# SpiCurrent-wimpy.net
KiCad netlist of a schematic drawn in EAGLE
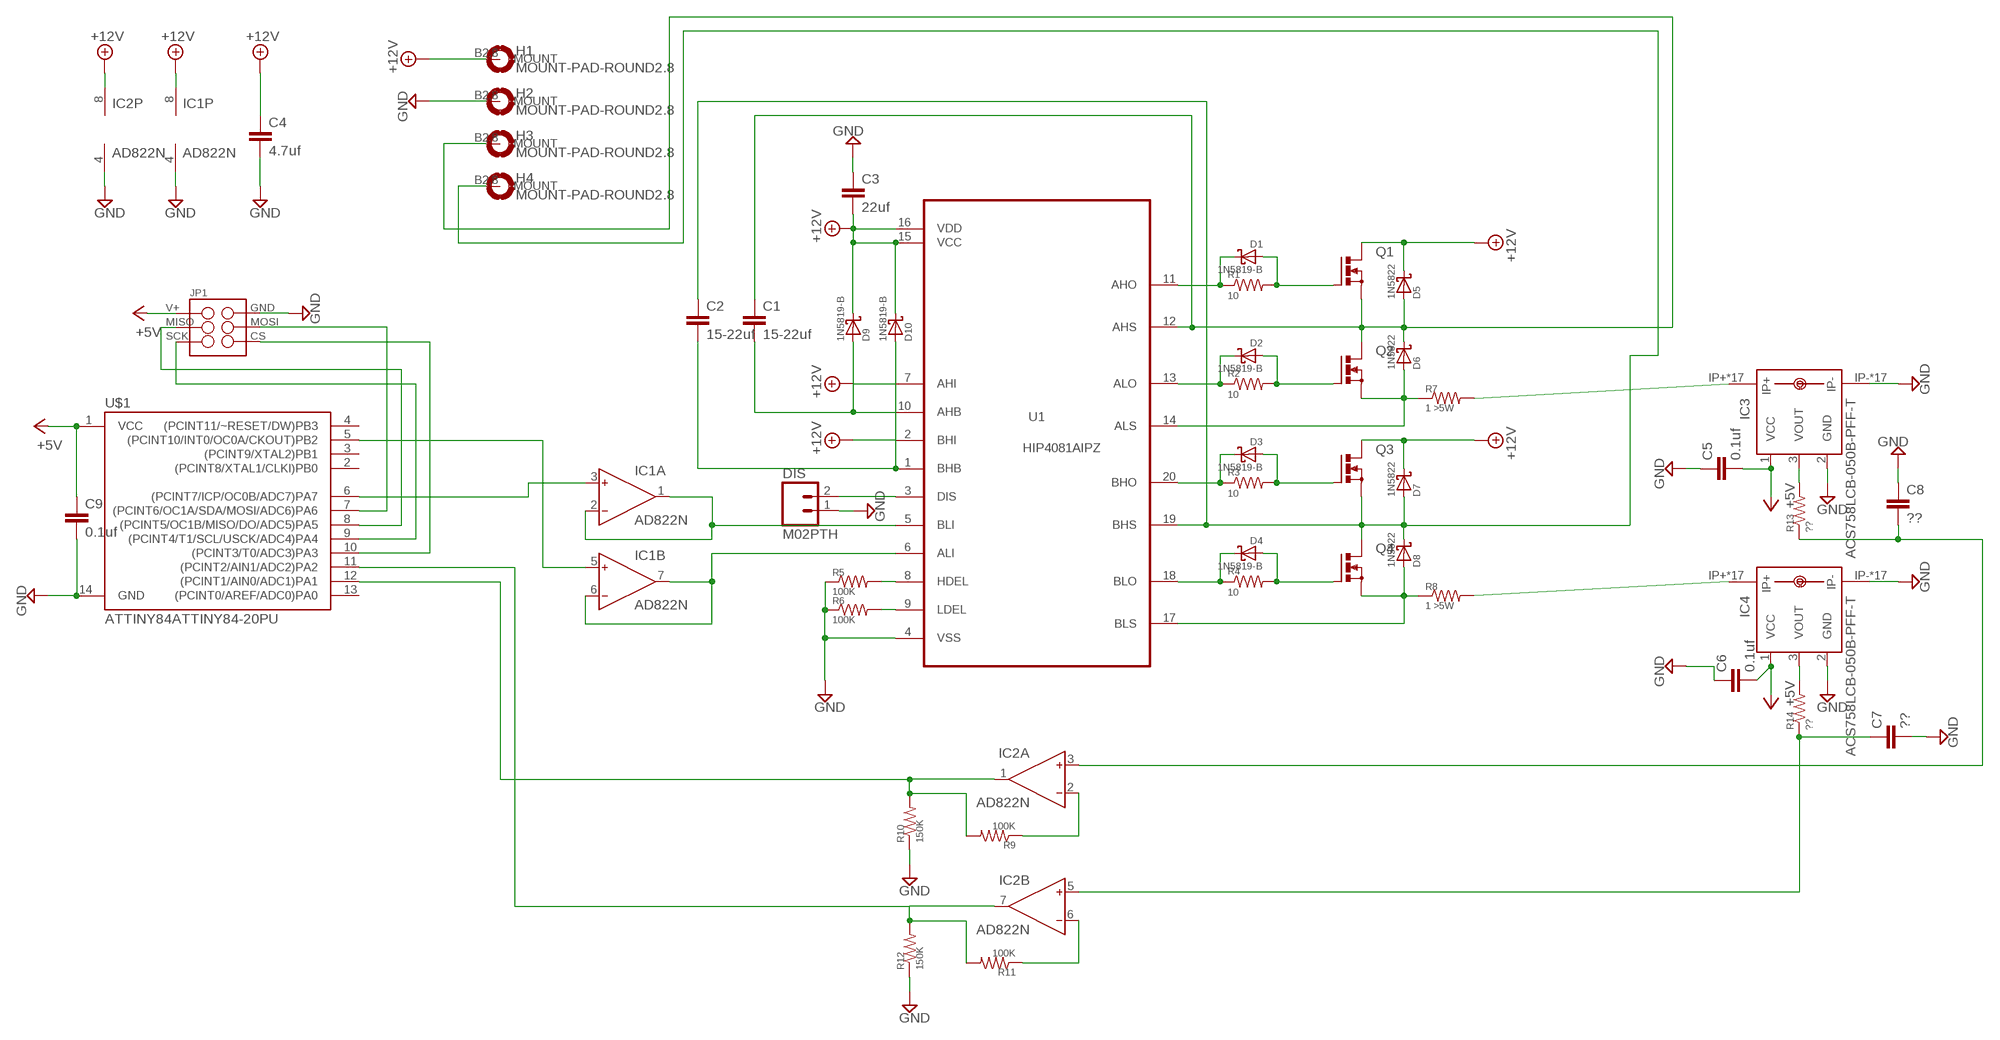
[diagram p0: schematic, sheet 1]

(export (version "E")
  (design (tool "Eeschema 10.0.6"))
  (components
    (comp (ref "C1")
      (value "15-22uf")
      (footprint "eagle-import:C050-055X075")
      (libsource (lib "eagle-import") (part "C-EU050-055X075"))
    )
    (comp (ref "C2")
      (value "15-22uf")
      (footprint "eagle-import:C050-055X075")
      (libsource (lib "eagle-import") (part "C-EU050-055X075"))
    )
    (comp (ref "C3")
      (value "22uf")
      (footprint "eagle-import:C050-055X075")
      (libsource (lib "eagle-import") (part "C-EU050-055X075"))
    )
    (comp (ref "C4")
      (value "4.7uf")
      (footprint "eagle-import:C050-055X075")
      (libsource (lib "eagle-import") (part "C-EU050-055X075"))
    )
    (comp (ref "C5")
      (value "0.1uf")
      (footprint "eagle-import:C050-055X075")
      (libsource (lib "eagle-import") (part "C-EU050-055X075"))
    )
    (comp (ref "C6")
      (value "0.1uf")
      (footprint "eagle-import:C050-055X075")
      (libsource (lib "eagle-import") (part "C-EU050-055X075"))
    )
    (comp (ref "C7")
      (value "??")
      (footprint "eagle-import:C050-055X075")
      (libsource (lib "eagle-import") (part "C-EU050-055X075"))
    )
    (comp (ref "C8")
      (value "??")
      (footprint "eagle-import:C050-055X075")
      (libsource (lib "eagle-import") (part "C-EU050-055X075"))
    )
    (comp (ref "C9")
      (value "0.1uf")
      (footprint "eagle-import:C050-055X075")
      (libsource (lib "eagle-import") (part "C-EU050-055X075"))
    )
    (comp (ref "D1")
      (value "1N5819-B")
      (footprint "eagle-import:DO41-7.6")
      (libsource (lib "eagle-import") (part "1N5819-B"))
    )
    (comp (ref "D2")
      (value "1N5819-B")
      (footprint "eagle-import:DO41-7.6")
      (libsource (lib "eagle-import") (part "1N5819-B"))
    )
    (comp (ref "D3")
      (value "1N5819-B")
      (footprint "eagle-import:DO41-7.6")
      (libsource (lib "eagle-import") (part "1N5819-B"))
    )
    (comp (ref "D4")
      (value "1N5819-B")
      (footprint "eagle-import:DO41-7.6")
      (libsource (lib "eagle-import") (part "1N5819-B"))
    )
    (comp (ref "D5")
      (value "1N5822")
      (footprint "eagle-import:DO41-7.6")
      (libsource (lib "eagle-import") (part "1N5819-B"))
    )
    (comp (ref "D6")
      (value "1N5822")
      (footprint "eagle-import:DO41-7.6")
      (libsource (lib "eagle-import") (part "1N5819-B"))
    )
    (comp (ref "D7")
      (value "1N5822")
      (footprint "eagle-import:DO41-7.6")
      (libsource (lib "eagle-import") (part "1N5819-B"))
    )
    (comp (ref "D8")
      (value "1N5822")
      (footprint "eagle-import:DO41-7.6")
      (libsource (lib "eagle-import") (part "1N5819-B"))
    )
    (comp (ref "D9")
      (value "1N5819-B")
      (footprint "eagle-import:DO41-7.6")
      (libsource (lib "eagle-import") (part "1N5819-B"))
    )
    (comp (ref "D10")
      (value "1N5819-B")
      (footprint "eagle-import:DO41-7.6")
      (libsource (lib "eagle-import") (part "1N5819-B"))
    )
    (comp (ref "DIS")
      (value "M02PTH")
      (footprint "eagle-import:1X02")
      (libsource (lib "eagle-import") (part "M02PTH"))
    )
    (comp (ref "H1")
      (value "MOUNT-PAD-ROUND2.8")
      (footprint "eagle-import:2,8-PAD")
      (libsource (lib "eagle-import") (part "MOUNT-PAD-ROUND2.8"))
    )
    (comp (ref "H2")
      (value "MOUNT-PAD-ROUND2.8")
      (footprint "eagle-import:2,8-PAD")
      (libsource (lib "eagle-import") (part "MOUNT-PAD-ROUND2.8"))
    )
    (comp (ref "H3")
      (value "MOUNT-PAD-ROUND2.8")
      (footprint "eagle-import:2,8-PAD")
      (libsource (lib "eagle-import") (part "MOUNT-PAD-ROUND2.8"))
    )
    (comp (ref "H4")
      (value "MOUNT-PAD-ROUND2.8")
      (footprint "eagle-import:2,8-PAD")
      (libsource (lib "eagle-import") (part "MOUNT-PAD-ROUND2.8"))
    )
    (comp (ref "IC1")
      (value "AD822N")
      (footprint "eagle-import:DIL08")
      (libsource (lib "eagle-import") (part "AD822N"))
    )
    (comp (ref "IC2")
      (value "AD822N")
      (footprint "eagle-import:DIL08")
      (libsource (lib "eagle-import") (part "AD822N"))
    )
    (comp (ref "IC3")
      (value "ACS758LCB-050B-PFF-T")
      (footprint "eagle-import:CB-PFF")
      (libsource (lib "eagle-import") (part "ACS758LCB-050B-PFF-T"))
    )
    (comp (ref "IC4")
      (value "ACS758LCB-050B-PFF-T")
      (footprint "eagle-import:CB-PFF")
      (libsource (lib "eagle-import") (part "ACS758LCB-050B-PFF-T"))
    )
    (comp (ref "JP1")
      (value "M03X2SHROUD")
      (footprint "eagle-import:2X3-SPI-SHROUDED")
      (libsource (lib "eagle-import") (part "M03X2SHROUD"))
    )
    (comp (ref "Q1")
      (value "PMOSFET_NTO220BV")
      (footprint "eagle-import:TO220BV")
      (libsource (lib "eagle-import") (part "PMOSFET_NTO220BV"))
    )
    (comp (ref "Q2")
      (value "PMOSFET_NTO220BV")
      (footprint "eagle-import:TO220BV")
      (libsource (lib "eagle-import") (part "PMOSFET_NTO220BV"))
    )
    (comp (ref "Q3")
      (value "PMOSFET_NTO220BV")
      (footprint "eagle-import:TO220BV")
      (libsource (lib "eagle-import") (part "PMOSFET_NTO220BV"))
    )
    (comp (ref "Q4")
      (value "PMOSFET_NTO220BV")
      (footprint "eagle-import:TO220BV")
      (libsource (lib "eagle-import") (part "PMOSFET_NTO220BV"))
    )
    (comp (ref "R1")
      (value "10")
      (footprint "eagle-import:0207_10")
      (libsource (lib "eagle-import") (part "R-US_0207/10"))
    )
    (comp (ref "R2")
      (value "10")
      (footprint "eagle-import:0207_10")
      (libsource (lib "eagle-import") (part "R-US_0207/10"))
    )
    (comp (ref "R3")
      (value "10")
      (footprint "eagle-import:0207_10")
      (libsource (lib "eagle-import") (part "R-US_0207/10"))
    )
    (comp (ref "R4")
      (value "10")
      (footprint "eagle-import:0207_10")
      (libsource (lib "eagle-import") (part "R-US_0207/10"))
    )
    (comp (ref "R5")
      (value "100K")
      (footprint "eagle-import:0207_10")
      (libsource (lib "eagle-import") (part "resistor-custom_R-US_0207/10"))
    )
    (comp (ref "R6")
      (value "100K")
      (footprint "eagle-import:0207_10")
      (libsource (lib "eagle-import") (part "resistor-custom_R-US_0207/10"))
    )
    (comp (ref "R7")
      (value "1 >5W")
      (footprint "eagle-import:VTA54")
      (libsource (lib "eagle-import") (part "resistor-custom_R-US_VTA54"))
    )
    (comp (ref "R8")
      (value "1 >5W")
      (footprint "eagle-import:VTA54")
      (libsource (lib "eagle-import") (part "resistor-custom_R-US_VTA54"))
    )
    (comp (ref "R9")
      (value "100K")
      (footprint "eagle-import:0207_10")
      (libsource (lib "eagle-import") (part "resistor-custom_R-US_0207/10"))
    )
    (comp (ref "R10")
      (value "150K")
      (footprint "eagle-import:0207_10")
      (libsource (lib "eagle-import") (part "resistor-custom_R-US_0207/10"))
    )
    (comp (ref "R11")
      (value "100K")
      (footprint "eagle-import:0207_10")
      (libsource (lib "eagle-import") (part "resistor-custom_R-US_0207/10"))
    )
    (comp (ref "R12")
      (value "150K")
      (footprint "eagle-import:0207_10")
      (libsource (lib "eagle-import") (part "resistor-custom_R-US_0207/10"))
    )
    (comp (ref "R13")
      (value "??")
      (footprint "eagle-import:0207_10")
      (libsource (lib "eagle-import") (part "resistor-custom_R-US_0207/10"))
    )
    (comp (ref "R14")
      (value "??")
      (footprint "eagle-import:0207_10")
      (libsource (lib "eagle-import") (part "resistor-custom_R-US_0207/10"))
    )
    (comp (ref "U$1")
      (value "ATTINY84ATTINY84-20PU")
      (footprint "eagle-import:DIL14")
      (libsource (lib "eagle-import") (part "ATTINY84ATTINY84-20PU"))
    )
    (comp (ref "U1")
      (value "HIP4081AIPZ")
      (footprint "eagle-import:DIP254P762X533-20")
      (libsource (lib "eagle-import") (part "HIP4081AIPZ"))
    )
  )
  (nets
    (net (code "1") (name "+5V") (class "Default")
      (node (ref "C5") (pin "2") (pinfunction "2_2") (pintype "passive"))
      (node (ref "C6") (pin "2") (pinfunction "2_2") (pintype "passive"))
      (node (ref "C9") (pin "1") (pinfunction "1_1") (pintype "passive"))
      (node (ref "IC3") (pin "1") (pinfunction "VCC_1") (pintype "power_in"))
      (node (ref "IC4") (pin "1") (pinfunction "VCC_1") (pintype "power_in"))
      (node (ref "JP1") (pin "1") (pinfunction "1_1") (pintype "bidirectional"))
      (node (ref "U$1") (pin "1") (pinfunction "VCC_1") (pintype "bidirectional"))
    )
    (net (code "2") (name "+12V") (class "Default")
      (node (ref "C3") (pin "2") (pinfunction "2_2") (pintype "passive"))
      (node (ref "C4") (pin "1") (pinfunction "1_1") (pintype "passive"))
      (node (ref "D10") (pin "C") (pinfunction "C_C") (pintype "passive"))
      (node (ref "D5") (pin "C") (pinfunction "C_C") (pintype "passive"))
      (node (ref "D7") (pin "C") (pinfunction "C_C") (pintype "passive"))
      (node (ref "D9") (pin "C") (pinfunction "C_C") (pintype "passive"))
      (node (ref "H1") (pin "B2,8") (pinfunction "MOUNT_B2,8") (pintype "passive"))
      (node (ref "IC1") (pin "8") (pinfunction "V+_8") (pintype "power_in"))
      (node (ref "IC2") (pin "8") (pinfunction "V+_8") (pintype "power_in"))
      (node (ref "Q1") (pin "D") (pinfunction "D_D") (pintype "passive"))
      (node (ref "Q3") (pin "D") (pinfunction "D_D") (pintype "passive"))
      (node (ref "U1") (pin "15") (pinfunction "VCC_15") (pintype "power_in"))
      (node (ref "U1") (pin "16") (pinfunction "VDD_16") (pintype "power_in"))
      (node (ref "U1") (pin "2") (pinfunction "BHI_2") (pintype "input"))
      (node (ref "U1") (pin "7") (pinfunction "AHI_7") (pintype "input"))
    )
    (net (code "3") (name "GND") (class "Default")
      (node (ref "C3") (pin "1") (pinfunction "1_1") (pintype "passive"))
      (node (ref "C4") (pin "2") (pinfunction "2_2") (pintype "passive"))
      (node (ref "C5") (pin "1") (pinfunction "1_1") (pintype "passive"))
      (node (ref "C6") (pin "1") (pinfunction "1_1") (pintype "passive"))
      (node (ref "C7") (pin "2") (pinfunction "2_2") (pintype "passive"))
      (node (ref "C8") (pin "1") (pinfunction "1_1") (pintype "passive"))
      (node (ref "C9") (pin "2") (pinfunction "2_2") (pintype "passive"))
      (node (ref "DIS") (pin "1") (pinfunction "1_1") (pintype "passive"))
      (node (ref "H2") (pin "B2,8") (pinfunction "MOUNT_B2,8") (pintype "passive"))
      (node (ref "IC1") (pin "4") (pinfunction "V-_4") (pintype "power_in"))
      (node (ref "IC2") (pin "4") (pinfunction "V-_4") (pintype "power_in"))
      (node (ref "IC3") (pin "2") (pinfunction "GND_2") (pintype "power_in"))
      (node (ref "IC3") (pin "IP-") (pinfunction "IP-_IP-") (pintype "passive"))
      (node (ref "IC3") (pin "IP-@10") (pinfunction "IP-_IP-@10") (pintype "passive"))
      (node (ref "IC3") (pin "IP-@11") (pinfunction "IP-_IP-@11") (pintype "passive"))
      (node (ref "IC3") (pin "IP-@12") (pinfunction "IP-_IP-@12") (pintype "passive"))
      (node (ref "IC3") (pin "IP-@13") (pinfunction "IP-_IP-@13") (pintype "passive"))
      (node (ref "IC3") (pin "IP-@14") (pinfunction "IP-_IP-@14") (pintype "passive"))
      (node (ref "IC3") (pin "IP-@15") (pinfunction "IP-_IP-@15") (pintype "passive"))
      (node (ref "IC3") (pin "IP-@16") (pinfunction "IP-_IP-@16") (pintype "passive"))
      (node (ref "IC3") (pin "IP-@17") (pinfunction "IP-_IP-@17") (pintype "passive"))
      (node (ref "IC3") (pin "IP-@2") (pinfunction "IP-_IP-@2") (pintype "passive"))
      (node (ref "IC3") (pin "IP-@3") (pinfunction "IP-_IP-@3") (pintype "passive"))
      (node (ref "IC3") (pin "IP-@4") (pinfunction "IP-_IP-@4") (pintype "passive"))
      (node (ref "IC3") (pin "IP-@5") (pinfunction "IP-_IP-@5") (pintype "passive"))
      (node (ref "IC3") (pin "IP-@6") (pinfunction "IP-_IP-@6") (pintype "passive"))
      (node (ref "IC3") (pin "IP-@7") (pinfunction "IP-_IP-@7") (pintype "passive"))
      (node (ref "IC3") (pin "IP-@8") (pinfunction "IP-_IP-@8") (pintype "passive"))
      (node (ref "IC3") (pin "IP-@9") (pinfunction "IP-_IP-@9") (pintype "passive"))
      (node (ref "IC4") (pin "2") (pinfunction "GND_2") (pintype "power_in"))
      (node (ref "IC4") (pin "IP-") (pinfunction "IP-_IP-") (pintype "passive"))
      (node (ref "IC4") (pin "IP-@10") (pinfunction "IP-_IP-@10") (pintype "passive"))
      (node (ref "IC4") (pin "IP-@11") (pinfunction "IP-_IP-@11") (pintype "passive"))
      (node (ref "IC4") (pin "IP-@12") (pinfunction "IP-_IP-@12") (pintype "passive"))
      (node (ref "IC4") (pin "IP-@13") (pinfunction "IP-_IP-@13") (pintype "passive"))
      (node (ref "IC4") (pin "IP-@14") (pinfunction "IP-_IP-@14") (pintype "passive"))
      (node (ref "IC4") (pin "IP-@15") (pinfunction "IP-_IP-@15") (pintype "passive"))
      (node (ref "IC4") (pin "IP-@16") (pinfunction "IP-_IP-@16") (pintype "passive"))
      (node (ref "IC4") (pin "IP-@17") (pinfunction "IP-_IP-@17") (pintype "passive"))
      (node (ref "IC4") (pin "IP-@2") (pinfunction "IP-_IP-@2") (pintype "passive"))
      (node (ref "IC4") (pin "IP-@3") (pinfunction "IP-_IP-@3") (pintype "passive"))
      (node (ref "IC4") (pin "IP-@4") (pinfunction "IP-_IP-@4") (pintype "passive"))
      (node (ref "IC4") (pin "IP-@5") (pinfunction "IP-_IP-@5") (pintype "passive"))
      (node (ref "IC4") (pin "IP-@6") (pinfunction "IP-_IP-@6") (pintype "passive"))
      (node (ref "IC4") (pin "IP-@7") (pinfunction "IP-_IP-@7") (pintype "passive"))
      (node (ref "IC4") (pin "IP-@8") (pinfunction "IP-_IP-@8") (pintype "passive"))
      (node (ref "IC4") (pin "IP-@9") (pinfunction "IP-_IP-@9") (pintype "passive"))
      (node (ref "JP1") (pin "2") (pinfunction "2_2") (pintype "bidirectional"))
      (node (ref "R10") (pin "1") (pinfunction "1_1") (pintype "passive"))
      (node (ref "R12") (pin "1") (pinfunction "1_1") (pintype "passive"))
      (node (ref "R5") (pin "1") (pinfunction "1_1") (pintype "passive"))
      (node (ref "R6") (pin "1") (pinfunction "1_1") (pintype "passive"))
      (node (ref "U$1") (pin "14") (pinfunction "GND_14") (pintype "bidirectional"))
      (node (ref "U1") (pin "4") (pinfunction "VSS_4") (pintype "power_in"))
    )
    (net (code "4") (name "Net-(D1-PadA)") (class "Default")
      (node (ref "D1") (pin "A") (pinfunction "A_A") (pintype "passive"))
      (node (ref "Q1") (pin "G") (pinfunction "G_G") (pintype "passive"))
      (node (ref "R1") (pin "2") (pinfunction "2_2") (pintype "passive"))
    )
    (net (code "5") (name "Net-(D2-PadA)") (class "Default")
      (node (ref "D2") (pin "A") (pinfunction "A_A") (pintype "passive"))
      (node (ref "Q2") (pin "G") (pinfunction "G_G") (pintype "passive"))
      (node (ref "R2") (pin "2") (pinfunction "2_2") (pintype "passive"))
    )
    (net (code "6") (name "Net-(D3-PadA)") (class "Default")
      (node (ref "D3") (pin "A") (pinfunction "A_A") (pintype "passive"))
      (node (ref "Q3") (pin "G") (pinfunction "G_G") (pintype "passive"))
      (node (ref "R3") (pin "2") (pinfunction "2_2") (pintype "passive"))
    )
    (net (code "7") (name "Net-(D4-PadA)") (class "Default")
      (node (ref "D4") (pin "A") (pinfunction "A_A") (pintype "passive"))
      (node (ref "Q4") (pin "G") (pinfunction "G_G") (pintype "passive"))
      (node (ref "R4") (pin "2") (pinfunction "2_2") (pintype "passive"))
    )
    (net (code "8") (name "Net-(H3-MOUNT)") (class "Default")
      (node (ref "C1") (pin "1") (pinfunction "1_1") (pintype "passive"))
      (node (ref "D5") (pin "A") (pinfunction "A_A") (pintype "passive"))
      (node (ref "D6") (pin "C") (pinfunction "C_C") (pintype "passive"))
      (node (ref "H3") (pin "B2,8") (pinfunction "MOUNT_B2,8") (pintype "passive"))
      (node (ref "Q1") (pin "S") (pinfunction "S_S") (pintype "passive"))
      (node (ref "Q2") (pin "D") (pinfunction "D_D") (pintype "passive"))
      (node (ref "U1") (pin "12") (pinfunction "AHS_12") (pintype "passive"))
    )
    (net (code "9") (name "Net-(H4-MOUNT)") (class "Default")
      (node (ref "C2") (pin "1") (pinfunction "1_1") (pintype "passive"))
      (node (ref "D7") (pin "A") (pinfunction "A_A") (pintype "passive"))
      (node (ref "D8") (pin "C") (pinfunction "C_C") (pintype "passive"))
      (node (ref "H4") (pin "B2,8") (pinfunction "MOUNT_B2,8") (pintype "passive"))
      (node (ref "Q3") (pin "S") (pinfunction "S_S") (pintype "passive"))
      (node (ref "Q4") (pin "D") (pinfunction "D_D") (pintype "passive"))
      (node (ref "U1") (pin "19") (pinfunction "BHS_19") (pintype "passive"))
    )
    (net (code "10") (name "Net-(IC1A-IN+)") (class "Default")
      (node (ref "IC1") (pin "3") (pinfunction "IN+_3") (pintype "input"))
      (node (ref "U$1") (pin "6") (pinfunction "(PCINT7/ICP/OC0B/ADC7)PA7_6") (pintype "bidirectional"))
    )
    (net (code "11") (name "Net-(IC1A-IN-)") (class "Default")
      (node (ref "IC1") (pin "1") (pinfunction "OUT_1") (pintype "output"))
      (node (ref "IC1") (pin "2") (pinfunction "IN-_2") (pintype "input"))
      (node (ref "U1") (pin "5") (pinfunction "BLI_5") (pintype "input"))
    )
    (net (code "12") (name "Net-(IC1B-IN+)") (class "Default")
      (node (ref "IC1") (pin "5") (pinfunction "IN+_5") (pintype "input"))
      (node (ref "U$1") (pin "5") (pinfunction "(PCINT10/INT0/OC0A/CKOUT)PB2_5") (pintype "bidirectional"))
    )
    (net (code "13") (name "Net-(IC1B-IN-)") (class "Default")
      (node (ref "IC1") (pin "6") (pinfunction "IN-_6") (pintype "input"))
      (node (ref "IC1") (pin "7") (pinfunction "OUT_7") (pintype "output"))
      (node (ref "U1") (pin "6") (pinfunction "ALI_6") (pintype "input"))
    )
    (net (code "14") (name "Net-(IC2A-IN+)") (class "Default")
      (node (ref "C8") (pin "2") (pinfunction "2_2") (pintype "passive"))
      (node (ref "IC2") (pin "3") (pinfunction "IN+_3") (pintype "input"))
      (node (ref "R13") (pin "1") (pinfunction "1_1") (pintype "passive"))
    )
    (net (code "15") (name "Net-(IC2A-IN-)") (class "Default")
      (node (ref "IC2") (pin "2") (pinfunction "IN-_2") (pintype "input"))
      (node (ref "R9") (pin "1") (pinfunction "1_1") (pintype "passive"))
    )
    (net (code "16") (name "Net-(IC2A-OUT)") (class "Default")
      (node (ref "IC2") (pin "1") (pinfunction "OUT_1") (pintype "output"))
      (node (ref "R10") (pin "2") (pinfunction "2_2") (pintype "passive"))
      (node (ref "R9") (pin "2") (pinfunction "2_2") (pintype "passive"))
      (node (ref "U$1") (pin "12") (pinfunction "(PCINT1/AIN0/ADC1)PA1_12") (pintype "bidirectional"))
    )
    (net (code "17") (name "Net-(IC2B-IN+)") (class "Default")
      (node (ref "C7") (pin "1") (pinfunction "1_1") (pintype "passive"))
      (node (ref "IC2") (pin "5") (pinfunction "IN+_5") (pintype "input"))
      (node (ref "R14") (pin "1") (pinfunction "1_1") (pintype "passive"))
    )
    (net (code "18") (name "Net-(IC2B-IN-)") (class "Default")
      (node (ref "IC2") (pin "6") (pinfunction "IN-_6") (pintype "input"))
      (node (ref "R11") (pin "1") (pinfunction "1_1") (pintype "passive"))
    )
    (net (code "19") (name "Net-(IC2B-OUT)") (class "Default")
      (node (ref "IC2") (pin "7") (pinfunction "OUT_7") (pintype "output"))
      (node (ref "R11") (pin "2") (pinfunction "2_2") (pintype "passive"))
      (node (ref "R12") (pin "2") (pinfunction "2_2") (pintype "passive"))
      (node (ref "U$1") (pin "11") (pinfunction "(PCINT2/AIN1/ADC2)PA2_11") (pintype "bidirectional"))
    )
    (net (code "20") (name "Net-(IC3-IP+-PadIP+@10)") (class "Default")
      (node (ref "IC3") (pin "IP+") (pinfunction "IP+_IP+") (pintype "passive"))
      (node (ref "IC3") (pin "IP+@10") (pinfunction "IP+_IP+@10") (pintype "passive"))
      (node (ref "IC3") (pin "IP+@11") (pinfunction "IP+_IP+@11") (pintype "passive"))
      (node (ref "IC3") (pin "IP+@12") (pinfunction "IP+_IP+@12") (pintype "passive"))
      (node (ref "IC3") (pin "IP+@13") (pinfunction "IP+_IP+@13") (pintype "passive"))
      (node (ref "IC3") (pin "IP+@14") (pinfunction "IP+_IP+@14") (pintype "passive"))
      (node (ref "IC3") (pin "IP+@15") (pinfunction "IP+_IP+@15") (pintype "passive"))
      (node (ref "IC3") (pin "IP+@16") (pinfunction "IP+_IP+@16") (pintype "passive"))
      (node (ref "IC3") (pin "IP+@17") (pinfunction "IP+_IP+@17") (pintype "passive"))
      (node (ref "IC3") (pin "IP+@2") (pinfunction "IP+_IP+@2") (pintype "passive"))
      (node (ref "IC3") (pin "IP+@3") (pinfunction "IP+_IP+@3") (pintype "passive"))
      (node (ref "IC3") (pin "IP+@4") (pinfunction "IP+_IP+@4") (pintype "passive"))
      (node (ref "IC3") (pin "IP+@5") (pinfunction "IP+_IP+@5") (pintype "passive"))
      (node (ref "IC3") (pin "IP+@6") (pinfunction "IP+_IP+@6") (pintype "passive"))
      (node (ref "IC3") (pin "IP+@7") (pinfunction "IP+_IP+@7") (pintype "passive"))
      (node (ref "IC3") (pin "IP+@8") (pinfunction "IP+_IP+@8") (pintype "passive"))
      (node (ref "IC3") (pin "IP+@9") (pinfunction "IP+_IP+@9") (pintype "passive"))
      (node (ref "R7") (pin "2") (pinfunction "2_2") (pintype "passive"))
    )
    (net (code "21") (name "Net-(IC3-VOUT)") (class "Default")
      (node (ref "IC3") (pin "3") (pinfunction "VOUT_3") (pintype "output"))
      (node (ref "R13") (pin "2") (pinfunction "2_2") (pintype "passive"))
    )
    (net (code "22") (name "Net-(IC4-IP+-PadIP+@10)") (class "Default")
      (node (ref "IC4") (pin "IP+") (pinfunction "IP+_IP+") (pintype "passive"))
      (node (ref "IC4") (pin "IP+@10") (pinfunction "IP+_IP+@10") (pintype "passive"))
      (node (ref "IC4") (pin "IP+@11") (pinfunction "IP+_IP+@11") (pintype "passive"))
      (node (ref "IC4") (pin "IP+@12") (pinfunction "IP+_IP+@12") (pintype "passive"))
      (node (ref "IC4") (pin "IP+@13") (pinfunction "IP+_IP+@13") (pintype "passive"))
      (node (ref "IC4") (pin "IP+@14") (pinfunction "IP+_IP+@14") (pintype "passive"))
      (node (ref "IC4") (pin "IP+@15") (pinfunction "IP+_IP+@15") (pintype "passive"))
      (node (ref "IC4") (pin "IP+@16") (pinfunction "IP+_IP+@16") (pintype "passive"))
      (node (ref "IC4") (pin "IP+@17") (pinfunction "IP+_IP+@17") (pintype "passive"))
      (node (ref "IC4") (pin "IP+@2") (pinfunction "IP+_IP+@2") (pintype "passive"))
      (node (ref "IC4") (pin "IP+@3") (pinfunction "IP+_IP+@3") (pintype "passive"))
      (node (ref "IC4") (pin "IP+@4") (pinfunction "IP+_IP+@4") (pintype "passive"))
      (node (ref "IC4") (pin "IP+@5") (pinfunction "IP+_IP+@5") (pintype "passive"))
      (node (ref "IC4") (pin "IP+@6") (pinfunction "IP+_IP+@6") (pintype "passive"))
      (node (ref "IC4") (pin "IP+@7") (pinfunction "IP+_IP+@7") (pintype "passive"))
      (node (ref "IC4") (pin "IP+@8") (pinfunction "IP+_IP+@8") (pintype "passive"))
      (node (ref "IC4") (pin "IP+@9") (pinfunction "IP+_IP+@9") (pintype "passive"))
      (node (ref "R8") (pin "2") (pinfunction "2_2") (pintype "passive"))
    )
    (net (code "23") (name "Net-(IC4-VOUT)") (class "Default")
      (node (ref "IC4") (pin "3") (pinfunction "VOUT_3") (pintype "output"))
      (node (ref "R14") (pin "2") (pinfunction "2_2") (pintype "passive"))
    )
    (net (code "24") (name "Net-(U$1-(PCINT3{slash}T0{slash}ADC3)PA3)") (class "Default")
      (node (ref "JP1") (pin "6") (pinfunction "6_6") (pintype "bidirectional"))
      (node (ref "U$1") (pin "10") (pinfunction "(PCINT3/T0/ADC3)PA3_10") (pintype "bidirectional"))
    )
    (net (code "25") (name "Net-(U$1-(PCINT4{slash}T1{slash}SCL{slash}USCK{slash}ADC4)PA4)") (class "Default")
      (node (ref "JP1") (pin "5") (pinfunction "5_5") (pintype "bidirectional"))
      (node (ref "U$1") (pin "9") (pinfunction "(PCINT4/T1/SCL/USCK/ADC4)PA4_9") (pintype "bidirectional"))
    )
    (net (code "26") (name "Net-(U$1-(PCINT5{slash}OC1B{slash}MISO{slash}DO{slash}ADC5)PA5)") (class "Default")
      (node (ref "JP1") (pin "3") (pinfunction "3_3") (pintype "bidirectional"))
      (node (ref "U$1") (pin "8") (pinfunction "(PCINT5/OC1B/MISO/DO/ADC5)PA5_8") (pintype "bidirectional"))
    )
    (net (code "27") (name "Net-(U$1-(PCINT6{slash}OC1A{slash}SDA{slash}MOSI{slash}ADC6)PA6)") (class "Default")
      (node (ref "JP1") (pin "4") (pinfunction "4_4") (pintype "bidirectional"))
      (node (ref "U$1") (pin "7") (pinfunction "(PCINT6/OC1A/SDA/MOSI/ADC6)PA6_7") (pintype "bidirectional"))
    )
    (net (code "28") (name "Net-(U1-AHB)") (class "Default")
      (node (ref "C1") (pin "2") (pinfunction "2_2") (pintype "passive"))
      (node (ref "D9") (pin "A") (pinfunction "A_A") (pintype "passive"))
      (node (ref "U1") (pin "10") (pinfunction "AHB_10") (pintype "input"))
    )
    (net (code "29") (name "Net-(U1-AHO)") (class "Default")
      (node (ref "D1") (pin "C") (pinfunction "C_C") (pintype "passive"))
      (node (ref "R1") (pin "1") (pinfunction "1_1") (pintype "passive"))
      (node (ref "U1") (pin "11") (pinfunction "AHO_11") (pintype "output"))
    )
    (net (code "30") (name "Net-(U1-ALO)") (class "Default")
      (node (ref "D2") (pin "C") (pinfunction "C_C") (pintype "passive"))
      (node (ref "R2") (pin "1") (pinfunction "1_1") (pintype "passive"))
      (node (ref "U1") (pin "13") (pinfunction "ALO_13") (pintype "output"))
    )
    (net (code "31") (name "Net-(U1-ALS)") (class "Default")
      (node (ref "D6") (pin "A") (pinfunction "A_A") (pintype "passive"))
      (node (ref "Q2") (pin "S") (pinfunction "S_S") (pintype "passive"))
      (node (ref "R7") (pin "1") (pinfunction "1_1") (pintype "passive"))
      (node (ref "U1") (pin "14") (pinfunction "ALS_14") (pintype "passive"))
    )
    (net (code "32") (name "Net-(U1-BHB)") (class "Default")
      (node (ref "C2") (pin "2") (pinfunction "2_2") (pintype "passive"))
      (node (ref "D10") (pin "A") (pinfunction "A_A") (pintype "passive"))
      (node (ref "U1") (pin "1") (pinfunction "BHB_1") (pintype "input"))
    )
    (net (code "33") (name "Net-(U1-BHO)") (class "Default")
      (node (ref "D3") (pin "C") (pinfunction "C_C") (pintype "passive"))
      (node (ref "R3") (pin "1") (pinfunction "1_1") (pintype "passive"))
      (node (ref "U1") (pin "20") (pinfunction "BHO_20") (pintype "output"))
    )
    (net (code "34") (name "Net-(U1-BLO)") (class "Default")
      (node (ref "D4") (pin "C") (pinfunction "C_C") (pintype "passive"))
      (node (ref "R4") (pin "1") (pinfunction "1_1") (pintype "passive"))
      (node (ref "U1") (pin "18") (pinfunction "BLO_18") (pintype "output"))
    )
    (net (code "35") (name "Net-(U1-BLS)") (class "Default")
      (node (ref "D8") (pin "A") (pinfunction "A_A") (pintype "passive"))
      (node (ref "Q4") (pin "S") (pinfunction "S_S") (pintype "passive"))
      (node (ref "R8") (pin "1") (pinfunction "1_1") (pintype "passive"))
      (node (ref "U1") (pin "17") (pinfunction "BLS_17") (pintype "passive"))
    )
    (net (code "36") (name "Net-(U1-DIS)") (class "Default")
      (node (ref "DIS") (pin "2") (pinfunction "2_2") (pintype "passive"))
      (node (ref "U1") (pin "3") (pinfunction "DIS_3") (pintype "input"))
    )
    (net (code "37") (name "Net-(U1-HDEL)") (class "Default")
      (node (ref "R5") (pin "2") (pinfunction "2_2") (pintype "passive"))
      (node (ref "U1") (pin "8") (pinfunction "HDEL_8") (pintype "input"))
    )
    (net (code "38") (name "Net-(U1-LDEL)") (class "Default")
      (node (ref "R6") (pin "2") (pinfunction "2_2") (pintype "passive"))
      (node (ref "U1") (pin "9") (pinfunction "LDEL_9") (pintype "input"))
    )
    (net (code "39") (name "unconnected-(U$1-(PCINT0{slash}AREF{slash}ADC0)PA0-Pad13)") (class "Default")
      (node (ref "U$1") (pin "13") (pinfunction "(PCINT0/AREF/ADC0)PA0_13") (pintype "bidirectional"))
    )
    (net (code "40") (name "unconnected-(U$1-(PCINT8{slash}XTAL1{slash}CLKI)PB0-Pad2)") (class "Default")
      (node (ref "U$1") (pin "2") (pinfunction "(PCINT8/XTAL1/CLKI)PB0_2") (pintype "bidirectional"))
    )
    (net (code "41") (name "unconnected-(U$1-(PCINT9{slash}XTAL2)PB1-Pad3)") (class "Default")
      (node (ref "U$1") (pin "3") (pinfunction "(PCINT9/XTAL2)PB1_3") (pintype "bidirectional"))
    )
    (net (code "42") (name "unconnected-(U$1-(PCINT11{slash}~{RESET{slash}DW})PB3-Pad4)") (class "Default")
      (node (ref "U$1") (pin "4") (pinfunction "(PCINT11/~{RESET/DW})PB3_4") (pintype "bidirectional"))
    )
  )
)
